# CSA.net
KiCad netlist of a schematic drawn in Altium Designer
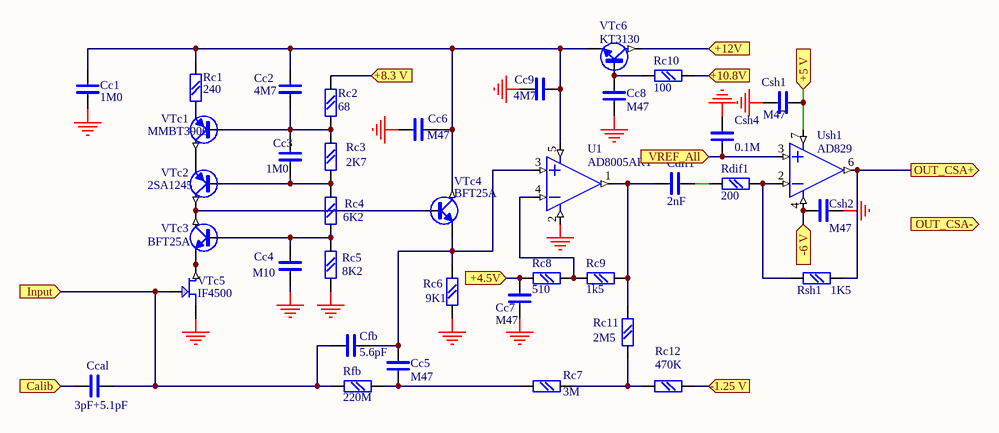
[diagram p0: CSA.SchDoc]

(export (version "E")
  (design (tool "Eeschema 10.0.6"))
  (components
    (comp (ref "Cc1") (value "1M0") (footprint "chip0805") (libsource (lib "*") (part "C")))
    (comp (ref "Cc2") (value "4M7") (footprint "chip0805") (libsource (lib "*") (part "C")))
    (comp (ref "Cc3") (value "1M0") (footprint "chip0805") (libsource (lib "*") (part "C")))
    (comp (ref "Cc4") (value "M10") (footprint "chip0805") (libsource (lib "*") (part "C")))
    (comp (ref "Cc5") (value "M47") (footprint "chip0805") (libsource (lib "*") (part "C")))
    (comp (ref "Cc6") (value "M47") (footprint "chip0805") (libsource (lib "*") (part "C")))
    (comp (ref "Cc7") (value "M47") (footprint "chip0805") (libsource (lib "*") (part "C")))
    (comp (ref "Cc8") (value "M47") (footprint "chip0805") (libsource (lib "*") (part "C")))
    (comp (ref "Cc9") (value "4M7") (footprint "chip1206") (libsource (lib "*") (part "C")))
    (comp (ref "Ccal") (value "3pF+5.1pF") (footprint "chip0805") (libsource (lib "*") (part "C")))
    (comp (ref "Cdif1") (value "2nF") (footprint "chip0805") (libsource (lib "*") (part "C")))
    (comp (ref "Cfb") (value "5.6pF") (footprint "chip0805") (libsource (lib "*") (part "C")))
    (comp (ref "Csh1") (value "M47") (footprint "chip0805") (libsource (lib "*") (part "C")))
    (comp (ref "Csh2") (value "M47") (footprint "chip0805") (libsource (lib "*") (part "C")))
    (comp (ref "Csh4") (value "0.1M") (footprint "chip0805") (libsource (lib "*") (part "C")))
    (comp (ref "Rc1") (value "240") (footprint "chip0805") (libsource (lib "*") (part "MLT")))
    (comp (ref "Rc2") (value "68") (footprint "chip0805") (libsource (lib "*") (part "MLT")))
    (comp (ref "Rc3") (value "2K7") (footprint "chip0805") (libsource (lib "*") (part "MLT")))
    (comp (ref "Rc4") (value "6K2") (footprint "chip0805") (libsource (lib "*") (part "MLT")))
    (comp (ref "Rc5") (value "8K2") (footprint "chip0805") (libsource (lib "*") (part "MLT")))
    (comp (ref "Rc6") (value "9K1") (footprint "chip0805") (libsource (lib "*") (part "MLT")))
    (comp (ref "Rc7") (value "3M") (footprint "chip0805") (libsource (lib "*") (part "MLT")))
    (comp (ref "Rc8") (value "510") (footprint "chip0805") (libsource (lib "*") (part "MLT")))
    (comp (ref "Rc9") (value "1k5") (footprint "chip0805") (libsource (lib "*") (part "MLT")))
    (comp (ref "Rc10") (value "100") (footprint "chip0805") (libsource (lib "*") (part "MLT")))
    (comp (ref "Rc11") (value "2M5") (footprint "chip0805") (libsource (lib "*") (part "MLT")))
    (comp (ref "Rc12") (value "470K") (footprint "chip0805") (libsource (lib "*") (part "MLT")))
    (comp (ref "Rdif1") (value "200") (footprint "chip0805") (libsource (lib "*") (part "R")))
    (comp (ref "Rfb") (value "220M") (footprint "chip1206") (libsource (lib "*") (part "MLT")))
    (comp (ref "Rsh1") (value "1K5") (footprint "chip0805") (libsource (lib "*") (part "R")))
    (comp (ref "U1") (value "AD8005ART") (footprint "SOT23-5") (libsource (lib "vAnalog") (part "AD8005ART")))
    (comp (ref "Ush1") (value "AD829") (footprint "Q16_2:8SO200") (libsource (lib "*") (part "AD8005")))
    (comp (ref "VTc1") (value "MMBT3906") (footprint "SOT23_bt") (libsource (lib "*") (part "$PNP")))
    (comp (ref "VTc2") (value "2SA1245") (footprint "SOT23_bt") (libsource (lib "*") (part "$PNP")))
    (comp (ref "VTc3") (value "BFT25A") (footprint "SOT23_bt") (libsource (lib "*") (part "$NPN")))
    (comp (ref "VTc4") (value "BFT25A") (footprint "SOT23_bt") (libsource (lib "*") (part "$NPN")))
    (comp (ref "VTc5") (value "IF4500") (footprint "SOT23_Fet") (libsource (lib "*") (part "$JFET N")))
    (comp (ref "VTc6") (value "KT3130") (footprint "SOT23_bt") (libsource (lib "*") (part "$NPN")))
  )
  (nets
    (net (code "1") (name "/+4.5V") (class "Default")
      (node (ref "Cc7") (pin "1") (pinfunction "1_1") (pintype "passive"))
      (node (ref "Rc8") (pin "1") (pinfunction "1_1") (pintype "passive"))
    )
    (net (code "2") (name "/+5 V") (class "Default")
      (node (ref "Csh1") (pin "1") (pinfunction "1_1") (pintype "passive"))
      (node (ref "Ush1") (pin "7") (pinfunction "E+_7") (pintype "input"))
    )
    (net (code "3") (name "/+8.3 V") (class "Default")
      (node (ref "Rc2") (pin "2") (pinfunction "2_2") (pintype "passive"))
    )
    (net (code "4") (name "/+10.8V") (class "Default")
      (node (ref "Rc10") (pin "2") (pinfunction "2_2") (pintype "passive"))
    )
    (net (code "5") (name "/+12V") (class "Default")
      (node (ref "VTc6") (pin "COLL") (pinfunction "COLL_COLL") (pintype "output"))
    )
    (net (code "6") (name "/-1.25 V") (class "Default")
      (node (ref "Rc12") (pin "2") (pinfunction "2_2") (pintype "passive"))
    )
    (net (code "7") (name "/-6 V") (class "Default")
      (node (ref "Csh2") (pin "2") (pinfunction "2_2") (pintype "passive"))
      (node (ref "Ush1") (pin "4") (pinfunction "E-_4") (pintype "input"))
    )
    (net (code "8") (name "/Calib") (class "Default")
      (node (ref "Ccal") (pin "1") (pinfunction "1_1") (pintype "passive"))
    )
    (net (code "9") (name "/Input") (class "Default")
      (node (ref "Ccal") (pin "2") (pinfunction "2_2") (pintype "passive"))
      (node (ref "Cfb") (pin "1") (pinfunction "1_1") (pintype "passive"))
      (node (ref "Rfb") (pin "1") (pinfunction "1_1") (pintype "passive"))
      (node (ref "VTc5") (pin "GATE") (pinfunction "GATE_GATE") (pintype "passive"))
    )
    (net (code "10") (name "/OUT_CSA+") (class "Default")
      (node (ref "Rsh1") (pin "2") (pinfunction "2_2") (pintype "passive"))
      (node (ref "Ush1") (pin "6") (pinfunction "OUT_6") (pintype "output"))
    )
    (net (code "12") (name "/VREF_All") (class "Default")
      (node (ref "Csh4") (pin "2") (pinfunction "2_2") (pintype "passive"))
      (node (ref "Ush1") (pin "3") (pinfunction "+IN_3") (pintype "input"))
    )
    (net (code "13") (name "GND") (class "Default")
      (node (ref "Cc1") (pin "1") (pinfunction "1_1") (pintype "passive"))
      (node (ref "Cc4") (pin "2") (pinfunction "2_2") (pintype "passive"))
      (node (ref "Cc6") (pin "1") (pinfunction "1_1") (pintype "passive"))
      (node (ref "Cc7") (pin "2") (pinfunction "2_2") (pintype "passive"))
      (node (ref "Cc8") (pin "2") (pinfunction "2_2") (pintype "passive"))
      (node (ref "Cc9") (pin "1") (pinfunction "1_1") (pintype "passive"))
      (node (ref "Csh1") (pin "2") (pinfunction "2_2") (pintype "passive"))
      (node (ref "Csh2") (pin "1") (pinfunction "1_1") (pintype "passive"))
      (node (ref "Csh4") (pin "1") (pinfunction "1_1") (pintype "passive"))
      (node (ref "Rc5") (pin "1") (pinfunction "1_1") (pintype "passive"))
      (node (ref "Rc6") (pin "2") (pinfunction "2_2") (pintype "passive"))
      (node (ref "U1") (pin "2") (pinfunction "E-_2") (pintype "input"))
      (node (ref "VTc5") (pin "SOUR") (pinfunction "SOUR_SOUR") (pintype "bidirectional"))
    )
    (net (code "14") (name "Net-(Cc2-Pad2)") (class "Default")
      (node (ref "Cc2") (pin "2") (pinfunction "2_2") (pintype "passive"))
      (node (ref "Cc3") (pin "1") (pinfunction "1_1") (pintype "passive"))
      (node (ref "Rc2") (pin "1") (pinfunction "1_1") (pintype "passive"))
      (node (ref "Rc3") (pin "1") (pinfunction "1_1") (pintype "passive"))
      (node (ref "VTc1") (pin "BASE") (pinfunction "BASE_BASE") (pintype "passive"))
    )
    (net (code "15") (name "Net-(Cc3-Pad2)") (class "Default")
      (node (ref "Cc3") (pin "2") (pinfunction "2_2") (pintype "passive"))
      (node (ref "Rc3") (pin "2") (pinfunction "2_2") (pintype "passive"))
      (node (ref "Rc4") (pin "1") (pinfunction "1_1") (pintype "passive"))
      (node (ref "VTc2") (pin "BASE") (pinfunction "BASE_BASE") (pintype "passive"))
    )
    (net (code "16") (name "Net-(Cc4-Pad1)") (class "Default")
      (node (ref "Cc4") (pin "1") (pinfunction "1_1") (pintype "passive"))
      (node (ref "Rc4") (pin "2") (pinfunction "2_2") (pintype "passive"))
      (node (ref "Rc5") (pin "2") (pinfunction "2_2") (pintype "passive"))
      (node (ref "VTc3") (pin "BASE") (pinfunction "BASE_BASE") (pintype "passive"))
    )
    (net (code "17") (name "Net-(Cc5-Pad2)") (class "Default")
      (node (ref "Cc5") (pin "2") (pinfunction "2_2") (pintype "passive"))
      (node (ref "Rc7") (pin "2") (pinfunction "2_2") (pintype "passive"))
      (node (ref "Rfb") (pin "2") (pinfunction "2_2") (pintype "passive"))
    )
    (net (code "18") (name "Net-(Cc8-Pad1)") (class "Default")
      (node (ref "Cc8") (pin "1") (pinfunction "1_1") (pintype "passive"))
      (node (ref "Rc10") (pin "1") (pinfunction "1_1") (pintype "passive"))
      (node (ref "VTc6") (pin "BASE") (pinfunction "BASE_BASE") (pintype "passive"))
    )
    (net (code "19") (name "Net-(Cdif1-Pad2)") (class "Default")
      (node (ref "Cdif1") (pin "2") (pinfunction "2_2") (pintype "passive"))
      (node (ref "Rdif1") (pin "1") (pinfunction "1_1") (pintype "passive"))
    )
    (net (code "20") (name "Net-(Rc1-Pad2)") (class "Default")
      (node (ref "Rc1") (pin "2") (pinfunction "2_2") (pintype "passive"))
      (node (ref "VTc1") (pin "EMIT") (pinfunction "EMIT_EMIT") (pintype "bidirectional"))
    )
    (net (code "21") (name "Net-(Rc11-Pad1)") (class "Default")
      (node (ref "Rc11") (pin "1") (pinfunction "1_1") (pintype "passive"))
      (node (ref "Rc12") (pin "1") (pinfunction "1_1") (pintype "passive"))
      (node (ref "Rc7") (pin "1") (pinfunction "1_1") (pintype "passive"))
    )
    (net (code "22") (name "Net-(U1-+IN)") (class "Default")
      (node (ref "Cc5") (pin "1") (pinfunction "1_1") (pintype "passive"))
      (node (ref "Cfb") (pin "2") (pinfunction "2_2") (pintype "passive"))
      (node (ref "Rc6") (pin "1") (pinfunction "1_1") (pintype "passive"))
      (node (ref "U1") (pin "3") (pinfunction "+IN_3") (pintype "input"))
      (node (ref "VTc4") (pin "EMIT") (pinfunction "EMIT_EMIT") (pintype "bidirectional"))
    )
    (net (code "23") (name "Net-(U1--IN)") (class "Default")
      (node (ref "Rc8") (pin "2") (pinfunction "2_2") (pintype "passive"))
      (node (ref "Rc9") (pin "1") (pinfunction "1_1") (pintype "passive"))
      (node (ref "U1") (pin "4") (pinfunction "-IN_4") (pintype "input"))
    )
    (net (code "24") (name "Net-(U1-E+)") (class "Default")
      (node (ref "Cc1") (pin "2") (pinfunction "2_2") (pintype "passive"))
      (node (ref "Cc2") (pin "1") (pinfunction "1_1") (pintype "passive"))
      (node (ref "Cc6") (pin "2") (pinfunction "2_2") (pintype "passive"))
      (node (ref "Cc9") (pin "2") (pinfunction "2_2") (pintype "passive"))
      (node (ref "Rc1") (pin "1") (pinfunction "1_1") (pintype "passive"))
      (node (ref "U1") (pin "5") (pinfunction "E+_5") (pintype "input"))
      (node (ref "VTc4") (pin "COLL") (pinfunction "COLL_COLL") (pintype "output"))
      (node (ref "VTc6") (pin "EMIT") (pinfunction "EMIT_EMIT") (pintype "bidirectional"))
    )
    (net (code "25") (name "Net-(U1-OUT)") (class "Default")
      (node (ref "Cdif1") (pin "1") (pinfunction "1_1") (pintype "passive"))
      (node (ref "Rc11") (pin "2") (pinfunction "2_2") (pintype "passive"))
      (node (ref "Rc9") (pin "2") (pinfunction "2_2") (pintype "passive"))
      (node (ref "U1") (pin "1") (pinfunction "OUT_1") (pintype "output"))
    )
    (net (code "26") (name "Net-(Ush1--IN)") (class "Default")
      (node (ref "Rdif1") (pin "2") (pinfunction "2_2") (pintype "passive"))
      (node (ref "Rsh1") (pin "1") (pinfunction "1_1") (pintype "passive"))
      (node (ref "Ush1") (pin "2") (pinfunction "-IN_2") (pintype "input"))
    )
    (net (code "27") (name "Net-(VTc1-PadCOLL)") (class "Default")
      (node (ref "VTc1") (pin "COLL") (pinfunction "COLL_COLL") (pintype "output"))
      (node (ref "VTc2") (pin "EMIT") (pinfunction "EMIT_EMIT") (pintype "bidirectional"))
    )
    (net (code "28") (name "Net-(VTc2-PadCOLL)") (class "Default")
      (node (ref "VTc2") (pin "COLL") (pinfunction "COLL_COLL") (pintype "output"))
      (node (ref "VTc3") (pin "COLL") (pinfunction "COLL_COLL") (pintype "output"))
      (node (ref "VTc4") (pin "BASE") (pinfunction "BASE_BASE") (pintype "passive"))
    )
    (net (code "29") (name "Net-(VTc3-PadEMIT)") (class "Default")
      (node (ref "VTc3") (pin "EMIT") (pinfunction "EMIT_EMIT") (pintype "bidirectional"))
      (node (ref "VTc5") (pin "DRAI") (pinfunction "DRAI_DRAI") (pintype "output"))
    )
  )
)
